# Truss-Power-V3.net
KiCad netlist of a schematic drawn in EAGLE
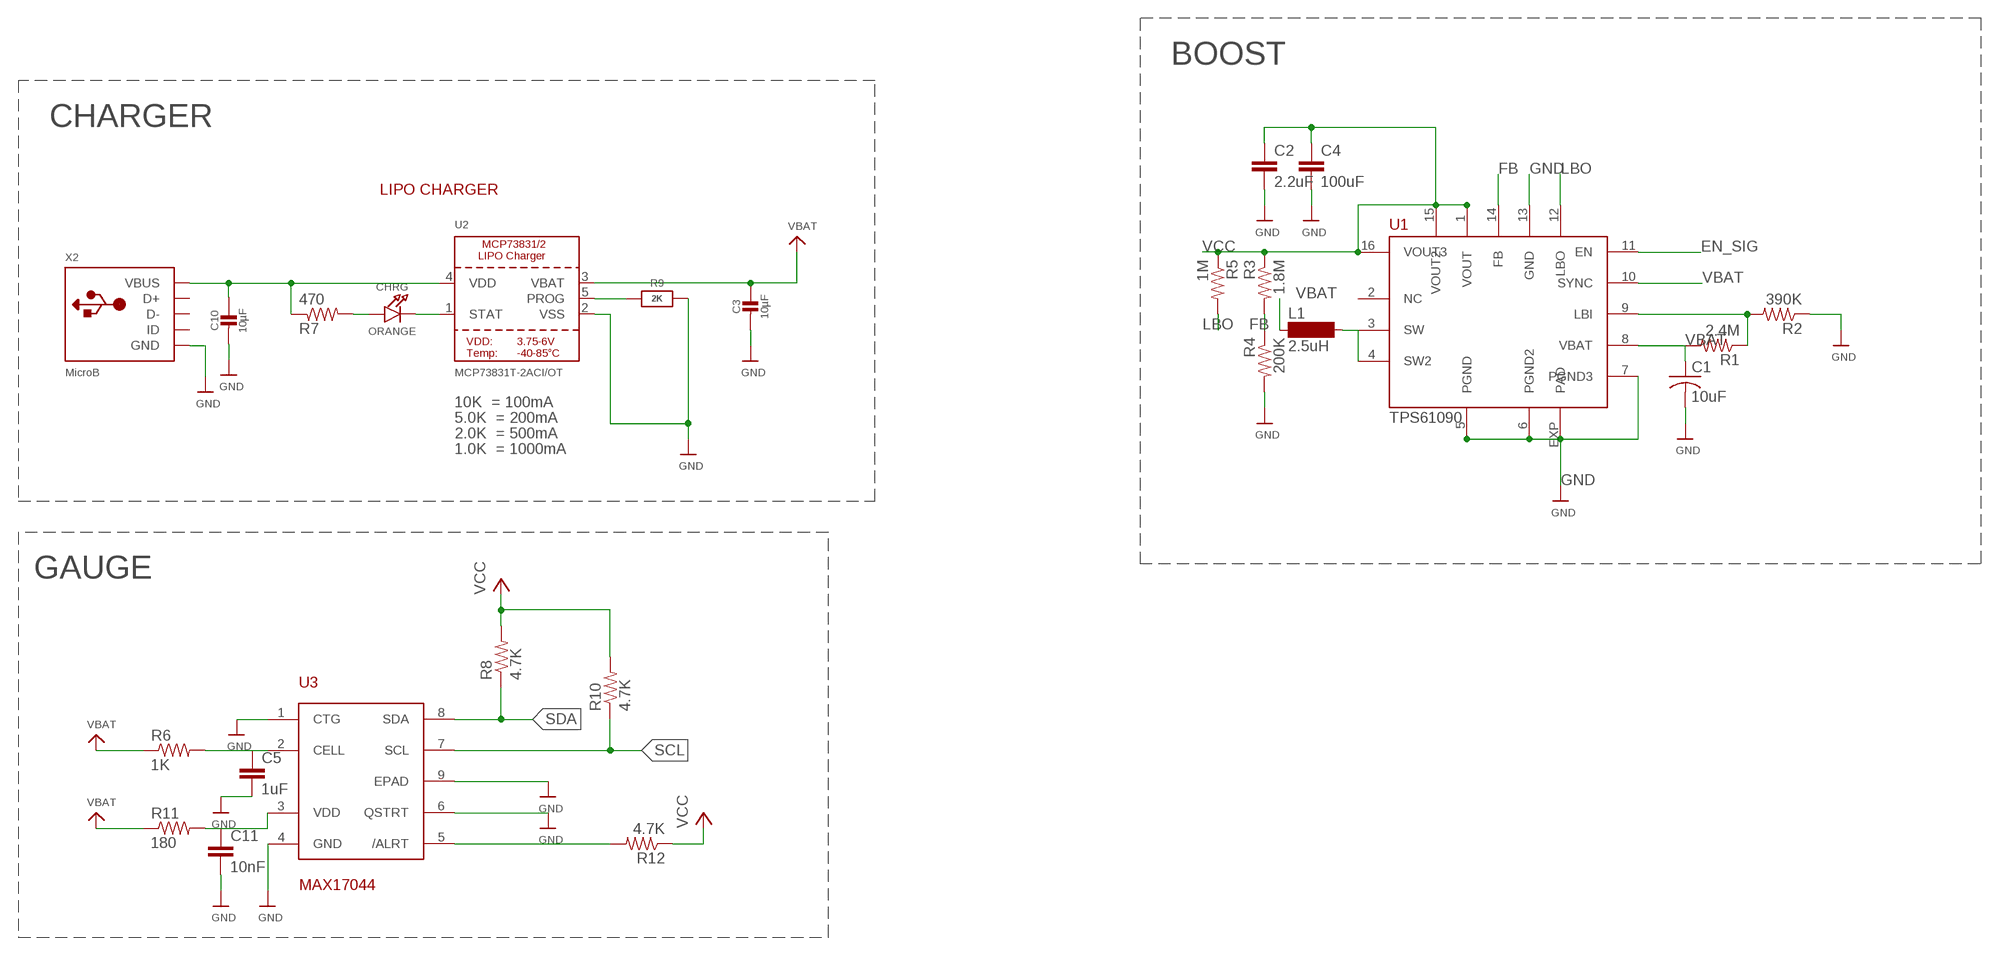
[diagram p0: schematic, sheet 1]
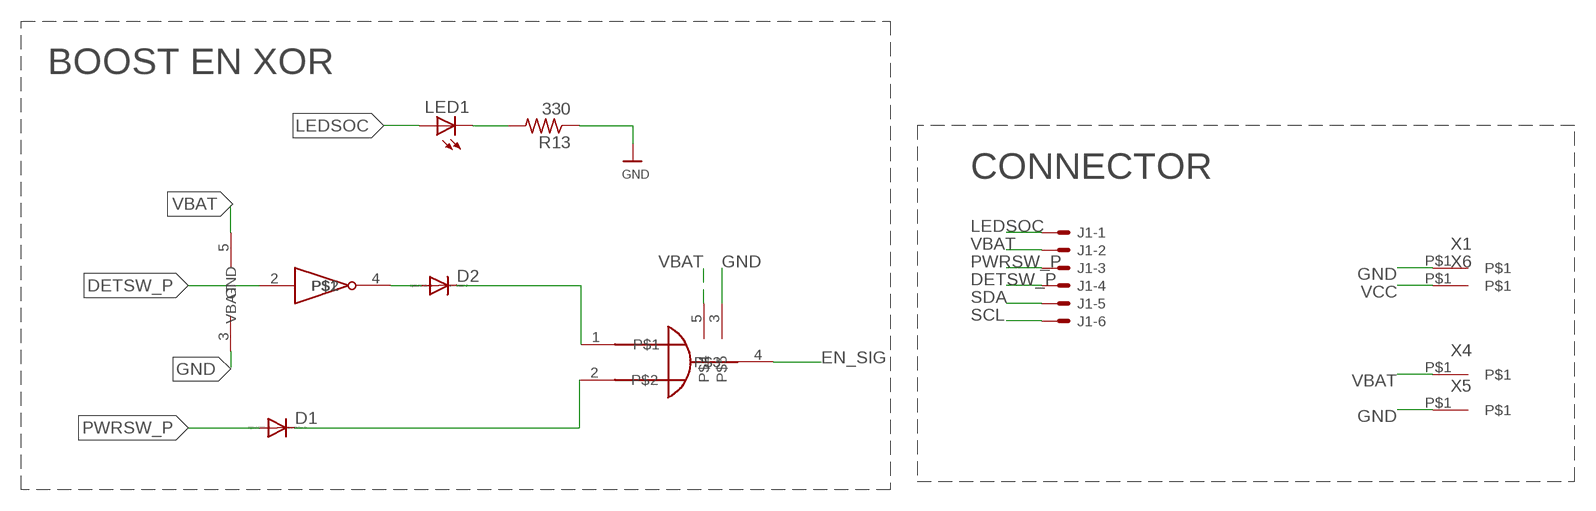
[diagram p1: schematic, sheet 2]

(export (version "E")
  (design (tool "Eeschema 10.0.6"))
  (components
    (comp (ref "D1")
      (value "DIODE-SOD523")
      (footprint "eagle-import:SOD523")
      (libsource (lib "eagle-import") (part "DIODE-SOD523"))
    )
    (comp (ref "D2")
      (value "DIODE-SOD523")
      (footprint "eagle-import:SOD523")
      (libsource (lib "eagle-import") (part "DIODE-SOD523"))
    )
    (comp (ref "J1")
      (value "XF2L-0625-1")
      (footprint "eagle-import:XF2L-0625-1")
      (fields (field (name "MF") "OMRON COMPONENTS USA"))
      (libsource (lib "eagle-import") (part "XF2-06?25-1L"))
    )
    (comp (ref "LED1")
      (value "LEDCHIP-LED0603")
      (footprint "eagle-import:CHIP-LED0603")
      (libsource (lib "eagle-import") (part "LEDCHIP-LED0603"))
    )
    (comp (ref "R13")
      (value "330")
      (footprint "eagle-import:R0402")
      (libsource (lib "eagle-import") (part "resistor_R-US_R0402"))
    )
    (comp (ref "U$16")
      (value "INVERTER-GATE")
      (footprint "eagle-import:SOC70-5")
      (libsource (lib "eagle-import") (part "INVERTER-GATE"))
    )
    (comp (ref "U4")
      (value "SN74LVC1G86DC1LR")
      (footprint "eagle-import:SOC70-5")
      (libsource (lib "eagle-import") (part "SN74LVC1G86DC1LR"))
    )
    (comp (ref "X1")
      (value "CON-1PIN")
      (footprint "eagle-import:CON-1PIN")
      (libsource (lib "eagle-import") (part "CON-1PIN"))
    )
    (comp (ref "X4")
      (value "CON-1PIN")
      (footprint "eagle-import:CON-1PIN")
      (libsource (lib "eagle-import") (part "CON-1PIN"))
    )
    (comp (ref "X5")
      (value "CON-1PIN")
      (footprint "eagle-import:CON-1PIN")
      (libsource (lib "eagle-import") (part "CON-1PIN"))
    )
    (comp (ref "X6")
      (value "CON-1PIN")
      (footprint "eagle-import:CON-1PIN")
      (libsource (lib "eagle-import") (part "CON-1PIN"))
    )
    (comp (ref "C1")
      (value "10uF")
      (footprint "eagle-import:C0805K")
      (libsource (lib "eagle-import") (part "C-USC0805K"))
    )
    (comp (ref "C2")
      (value "2.2uF")
      (footprint "eagle-import:C0805K")
      (libsource (lib "eagle-import") (part "C-EUC0805K"))
    )
    (comp (ref "C3")
      (value "10µF")
      (footprint "eagle-import:0805-NO")
      (libsource (lib "eagle-import") (part "CAP_CERAMIC0805-NOOUTLINE"))
    )
    (comp (ref "C4")
      (value "100uF")
      (footprint "eagle-import:7343-METRIC")
      (libsource (lib "eagle-import") (part "TANT-CAP"))
    )
    (comp (ref "C5")
      (value "1uF")
      (footprint "eagle-import:C0603")
      (libsource (lib "eagle-import") (part "C-EUC0603"))
    )
    (comp (ref "C10")
      (value "10µF")
      (footprint "eagle-import:0805-NO")
      (libsource (lib "eagle-import") (part "CAP_CERAMIC0805-NOOUTLINE"))
    )
    (comp (ref "C11")
      (value "10nF")
      (footprint "eagle-import:C0603")
      (libsource (lib "eagle-import") (part "C-EUC0603"))
    )
    (comp (ref "CHRG")
      (value "ORANGE")
      (footprint "eagle-import:CHIPLED_0805_NOOUTLINE")
      (libsource (lib "eagle-import") (part "LED0805_NOOUTLINE"))
    )
    (comp (ref "L1")
      (value "2.5uH")
      (footprint "eagle-import:CDRH5D28")
      (libsource (lib "eagle-import") (part "CDRH5D28"))
    )
    (comp (ref "R1")
      (value "2.4M")
      (footprint "eagle-import:R0603")
      (libsource (lib "eagle-import") (part "R-US_R0603"))
    )
    (comp (ref "R2")
      (value "390K")
      (footprint "eagle-import:R0603")
      (libsource (lib "eagle-import") (part "R-US_R0603"))
    )
    (comp (ref "R3")
      (value "1.8M")
      (footprint "eagle-import:R0603")
      (libsource (lib "eagle-import") (part "R-US_R0603"))
    )
    (comp (ref "R4")
      (value "200K")
      (footprint "eagle-import:R0603")
      (libsource (lib "eagle-import") (part "R-US_R0603"))
    )
    (comp (ref "R5")
      (value "1M")
      (footprint "eagle-import:R0603")
      (libsource (lib "eagle-import") (part "R-US_R0603"))
    )
    (comp (ref "R6")
      (value "1K")
      (footprint "eagle-import:R0402")
      (libsource (lib "eagle-import") (part "resistor_R-US_R0402"))
    )
    (comp (ref "R7")
      (value "470")
      (footprint "eagle-import:R0402")
      (libsource (lib "eagle-import") (part "resistor_R-US_R0402"))
    )
    (comp (ref "R8")
      (value "4.7K")
      (footprint "eagle-import:R0402")
      (libsource (lib "eagle-import") (part "resistor_R-US_R0402"))
    )
    (comp (ref "R9")
      (value "2K")
      (footprint "eagle-import:0805-NO")
      (libsource (lib "eagle-import") (part "RESISTOR0805_NOOUTLINE"))
    )
    (comp (ref "R10")
      (value "4.7K")
      (footprint "eagle-import:R0402")
      (libsource (lib "eagle-import") (part "resistor_R-US_R0402"))
    )
    (comp (ref "R11")
      (value "180")
      (footprint "eagle-import:R0402")
      (libsource (lib "eagle-import") (part "resistor_R-US_R0402"))
    )
    (comp (ref "R12")
      (value "4.7K")
      (footprint "eagle-import:R0402")
      (libsource (lib "eagle-import") (part "resistor_R-US_R0402"))
    )
    (comp (ref "U1")
      (value "TPS61090")
      (footprint "eagle-import:TPS61090")
      (libsource (lib "eagle-import") (part "TPS61090"))
    )
    (comp (ref "U2")
      (value "MCP73831T-2ACI/OT")
      (footprint "eagle-import:SOT23-5")
      (libsource (lib "eagle-import") (part "MCP73831/2"))
    )
    (comp (ref "U3")
      (value "MAX17044")
      (footprint "eagle-import:TDFN")
      (libsource (lib "eagle-import") (part "MAX17044"))
    )
    (comp (ref "X2")
      (value "MicroB")
      (footprint "eagle-import:4UCONN_20329")
      (libsource (lib "eagle-import") (part "USBMICRO_20329"))
    )
  )
  (nets
    (net (code "1") (name "DETSW_P") (class "Default")
      (node (ref "J1") (pin "4") (pinfunction "MS_4") (pintype "passive"))
      (node (ref "U$16") (pin "2") (pinfunction "P$1_2") (pintype "bidirectional"))
    )
    (net (code "2") (name "EN_SIG") (class "Default")
      (node (ref "U1") (pin "11") (pinfunction "EN_11") (pintype "bidirectional"))
      (node (ref "U4") (pin "4") (pinfunction "P$3_4") (pintype "bidirectional"))
    )
    (net (code "3") (name "FB") (class "Default")
      (node (ref "R3") (pin "2") (pinfunction "2_2") (pintype "passive"))
      (node (ref "R4") (pin "1") (pinfunction "1_1") (pintype "passive"))
      (node (ref "U1") (pin "14") (pinfunction "FB_14") (pintype "bidirectional"))
    )
    (net (code "4") (name "GND") (class "Default")
      (node (ref "C1") (pin "2") (pinfunction "2_2") (pintype "passive"))
      (node (ref "C10") (pin "2") (pinfunction "2_2") (pintype "passive"))
      (node (ref "C11") (pin "2") (pinfunction "2_2") (pintype "passive"))
      (node (ref "C2") (pin "2") (pinfunction "2_2") (pintype "passive"))
      (node (ref "C3") (pin "2") (pinfunction "2_2") (pintype "passive"))
      (node (ref "C4") (pin "2") (pinfunction "2_2") (pintype "passive"))
      (node (ref "C5") (pin "2") (pinfunction "2_2") (pintype "passive"))
      (node (ref "R13") (pin "1") (pinfunction "1_1") (pintype "passive"))
      (node (ref "R2") (pin "1") (pinfunction "1_1") (pintype "passive"))
      (node (ref "R4") (pin "2") (pinfunction "2_2") (pintype "passive"))
      (node (ref "R9") (pin "2") (pinfunction "2_2") (pintype "passive"))
      (node (ref "U$16") (pin "3") (pinfunction "GND_3") (pintype "bidirectional"))
      (node (ref "U1") (pin "13") (pinfunction "GND_13") (pintype "bidirectional"))
      (node (ref "U1") (pin "5") (pinfunction "PGND_5") (pintype "bidirectional"))
      (node (ref "U1") (pin "6") (pinfunction "PGND2_6") (pintype "bidirectional"))
      (node (ref "U1") (pin "7") (pinfunction "PGND3_7") (pintype "bidirectional"))
      (node (ref "U1") (pin "EXP") (pinfunction "PAD_EXP") (pintype "bidirectional"))
      (node (ref "U2") (pin "2") (pinfunction "VSS_2") (pintype "power_in"))
      (node (ref "U3") (pin "1") (pinfunction "CTG_1") (pintype "bidirectional"))
      (node (ref "U3") (pin "4") (pinfunction "GND_4") (pintype "bidirectional"))
      (node (ref "U3") (pin "6") (pinfunction "QSTRT_6") (pintype "bidirectional"))
      (node (ref "U3") (pin "9") (pinfunction "EPAD_9") (pintype "bidirectional"))
      (node (ref "U4") (pin "3") (pinfunction "P$5_3") (pintype "bidirectional"))
      (node (ref "X1") (pin "P$1") (pinfunction "P$1_P$1") (pintype "bidirectional"))
      (node (ref "X2") (pin "BASE@1") (pinfunction "GND_BASE@1") (pintype "power_in"))
      (node (ref "X2") (pin "BASE@2") (pinfunction "GND_BASE@2") (pintype "power_in"))
      (node (ref "X2") (pin "GND") (pinfunction "GND_GND") (pintype "power_in"))
      (node (ref "X2") (pin "SPRT@1") (pinfunction "GND_SPRT@1") (pintype "power_in"))
      (node (ref "X2") (pin "SPRT@2") (pinfunction "GND_SPRT@2") (pintype "power_in"))
      (node (ref "X2") (pin "SPRT@3") (pinfunction "GND_SPRT@3") (pintype "power_in"))
      (node (ref "X2") (pin "SPRT@4") (pinfunction "GND_SPRT@4") (pintype "power_in"))
      (node (ref "X5") (pin "P$1") (pinfunction "P$1_P$1") (pintype "bidirectional"))
    )
    (net (code "5") (name "LBO") (class "Default")
      (node (ref "R5") (pin "2") (pinfunction "2_2") (pintype "passive"))
      (node (ref "U1") (pin "12") (pinfunction "LBO_12") (pintype "bidirectional"))
    )
    (net (code "6") (name "LEDSOC") (class "Default")
      (node (ref "J1") (pin "1") (pinfunction "MS_1") (pintype "passive"))
      (node (ref "LED1") (pin "A") (pinfunction "A_A") (pintype "passive"))
    )
    (net (code "7") (name "Net-(CHRG-PadA)") (class "Default")
      (node (ref "CHRG") (pin "A") (pinfunction "A_A") (pintype "passive"))
      (node (ref "R7") (pin "2") (pinfunction "2_2") (pintype "passive"))
    )
    (net (code "8") (name "Net-(LED1-PadC)") (class "Default")
      (node (ref "LED1") (pin "C") (pinfunction "C_C") (pintype "passive"))
      (node (ref "R13") (pin "2") (pinfunction "2_2") (pintype "passive"))
    )
    (net (code "9") (name "Net-(U$16-P$2)") (class "Default")
      (node (ref "D2") (pin "A") (pinfunction "A_A") (pintype "passive"))
      (node (ref "U$16") (pin "4") (pinfunction "P$2_4") (pintype "bidirectional"))
    )
    (net (code "10") (name "Net-(U1-LBI)") (class "Default")
      (node (ref "R1") (pin "1") (pinfunction "1_1") (pintype "passive"))
      (node (ref "R2") (pin "2") (pinfunction "2_2") (pintype "passive"))
      (node (ref "U1") (pin "9") (pinfunction "LBI_9") (pintype "bidirectional"))
    )
    (net (code "11") (name "Net-(U1-SW)") (class "Default")
      (node (ref "L1") (pin "2") (pinfunction "2_2") (pintype "passive"))
      (node (ref "U1") (pin "3") (pinfunction "SW_3") (pintype "bidirectional"))
      (node (ref "U1") (pin "4") (pinfunction "SW2_4") (pintype "bidirectional"))
    )
    (net (code "12") (name "Net-(U2-PROG)") (class "Default")
      (node (ref "R9") (pin "1") (pinfunction "1_1") (pintype "passive"))
      (node (ref "U2") (pin "5") (pinfunction "PROG_5") (pintype "input"))
    )
    (net (code "13") (name "Net-(U2-STAT)") (class "Default")
      (node (ref "CHRG") (pin "C") (pinfunction "C_C") (pintype "passive"))
      (node (ref "U2") (pin "1") (pinfunction "STAT_1") (pintype "output"))
    )
    (net (code "14") (name "Net-(U2-VDD)") (class "Default")
      (node (ref "C10") (pin "1") (pinfunction "1_1") (pintype "passive"))
      (node (ref "R7") (pin "1") (pinfunction "1_1") (pintype "passive"))
      (node (ref "U2") (pin "4") (pinfunction "VDD_4") (pintype "power_in"))
      (node (ref "X2") (pin "VBUS") (pinfunction "VBUS_VBUS") (pintype "power_in"))
    )
    (net (code "15") (name "Net-(U3-CELL)") (class "Default")
      (node (ref "C5") (pin "1") (pinfunction "1_1") (pintype "passive"))
      (node (ref "R6") (pin "2") (pinfunction "2_2") (pintype "passive"))
      (node (ref "U3") (pin "2") (pinfunction "CELL_2") (pintype "bidirectional"))
    )
    (net (code "16") (name "Net-(U3-VDD)") (class "Default")
      (node (ref "C11") (pin "1") (pinfunction "1_1") (pintype "passive"))
      (node (ref "R11") (pin "2") (pinfunction "2_2") (pintype "passive"))
      (node (ref "U3") (pin "3") (pinfunction "VDD_3") (pintype "bidirectional"))
    )
    (net (code "17") (name "Net-(U3-{slash}ALRT)") (class "Default")
      (node (ref "R12") (pin "2") (pinfunction "2_2") (pintype "passive"))
      (node (ref "U3") (pin "5") (pinfunction "/ALRT_5") (pintype "bidirectional"))
    )
    (net (code "18") (name "Net-(U4-P$1)") (class "Default")
      (node (ref "D2") (pin "C") (pinfunction "C_C") (pintype "passive"))
      (node (ref "U4") (pin "1") (pinfunction "P$1_1") (pintype "bidirectional"))
    )
    (net (code "19") (name "Net-(U4-P$2)") (class "Default")
      (node (ref "D1") (pin "C") (pinfunction "C_C") (pintype "passive"))
      (node (ref "U4") (pin "2") (pinfunction "P$2_2") (pintype "bidirectional"))
    )
    (net (code "20") (name "PWRSW_P") (class "Default")
      (node (ref "D1") (pin "A") (pinfunction "A_A") (pintype "passive"))
      (node (ref "J1") (pin "3") (pinfunction "MS_3") (pintype "passive"))
    )
    (net (code "21") (name "SCL") (class "Default")
      (node (ref "J1") (pin "6") (pinfunction "MS_6") (pintype "passive"))
      (node (ref "R10") (pin "1") (pinfunction "1_1") (pintype "passive"))
      (node (ref "U3") (pin "7") (pinfunction "SCL_7") (pintype "bidirectional"))
    )
    (net (code "22") (name "SDA") (class "Default")
      (node (ref "J1") (pin "5") (pinfunction "MS_5") (pintype "passive"))
      (node (ref "R8") (pin "1") (pinfunction "1_1") (pintype "passive"))
      (node (ref "U3") (pin "8") (pinfunction "SDA_8") (pintype "bidirectional"))
    )
    (net (code "23") (name "VBAT") (class "Default")
      (node (ref "C1") (pin "1") (pinfunction "1_1") (pintype "passive"))
      (node (ref "C3") (pin "1") (pinfunction "1_1") (pintype "passive"))
      (node (ref "J1") (pin "2") (pinfunction "MS_2") (pintype "passive"))
      (node (ref "L1") (pin "1") (pinfunction "1_1") (pintype "passive"))
      (node (ref "R1") (pin "2") (pinfunction "2_2") (pintype "passive"))
      (node (ref "R11") (pin "1") (pinfunction "1_1") (pintype "passive"))
      (node (ref "R6") (pin "1") (pinfunction "1_1") (pintype "passive"))
      (node (ref "U$16") (pin "5") (pinfunction "VBAT_5") (pintype "bidirectional"))
      (node (ref "U1") (pin "10") (pinfunction "SYNC_10") (pintype "bidirectional"))
      (node (ref "U1") (pin "8") (pinfunction "VBAT_8") (pintype "bidirectional"))
      (node (ref "U2") (pin "3") (pinfunction "VBAT_3") (pintype "power_in"))
      (node (ref "U4") (pin "5") (pinfunction "P$4_5") (pintype "bidirectional"))
      (node (ref "X4") (pin "P$1") (pinfunction "P$1_P$1") (pintype "bidirectional"))
    )
    (net (code "24") (name "VCC") (class "Default")
      (node (ref "C2") (pin "1") (pinfunction "1_1") (pintype "passive"))
      (node (ref "C4") (pin "1") (pinfunction "1_1") (pintype "passive"))
      (node (ref "R10") (pin "2") (pinfunction "2_2") (pintype "passive"))
      (node (ref "R12") (pin "1") (pinfunction "1_1") (pintype "passive"))
      (node (ref "R3") (pin "1") (pinfunction "1_1") (pintype "passive"))
      (node (ref "R5") (pin "1") (pinfunction "1_1") (pintype "passive"))
      (node (ref "R8") (pin "2") (pinfunction "2_2") (pintype "passive"))
      (node (ref "U1") (pin "1") (pinfunction "VOUT_1") (pintype "bidirectional"))
      (node (ref "U1") (pin "15") (pinfunction "VOUT2_15") (pintype "bidirectional"))
      (node (ref "U1") (pin "16") (pinfunction "VOUT3_16") (pintype "bidirectional"))
      (node (ref "X6") (pin "P$1") (pinfunction "P$1_P$1") (pintype "bidirectional"))
    )
    (net (code "25") (name "unconnected-(U1-NC-Pad2)") (class "Default")
      (node (ref "U1") (pin "2") (pinfunction "NC_2") (pintype "bidirectional"))
    )
    (net (code "26") (name "unconnected-(X2-PadD+)") (class "Default")
      (node (ref "X2") (pin "D+") (pinfunction "D+_D+") (pintype "bidirectional"))
    )
    (net (code "27") (name "unconnected-(X2-PadD-)") (class "Default")
      (node (ref "X2") (pin "D-") (pinfunction "D-_D-") (pintype "bidirectional"))
    )
    (net (code "28") (name "unconnected-(X2-PadID)") (class "Default")
      (node (ref "X2") (pin "ID") (pinfunction "ID_ID") (pintype "bidirectional"))
    )
  )
)
